# control_board_WS2812.net
KiCad netlist of a schematic drawn in EAGLE
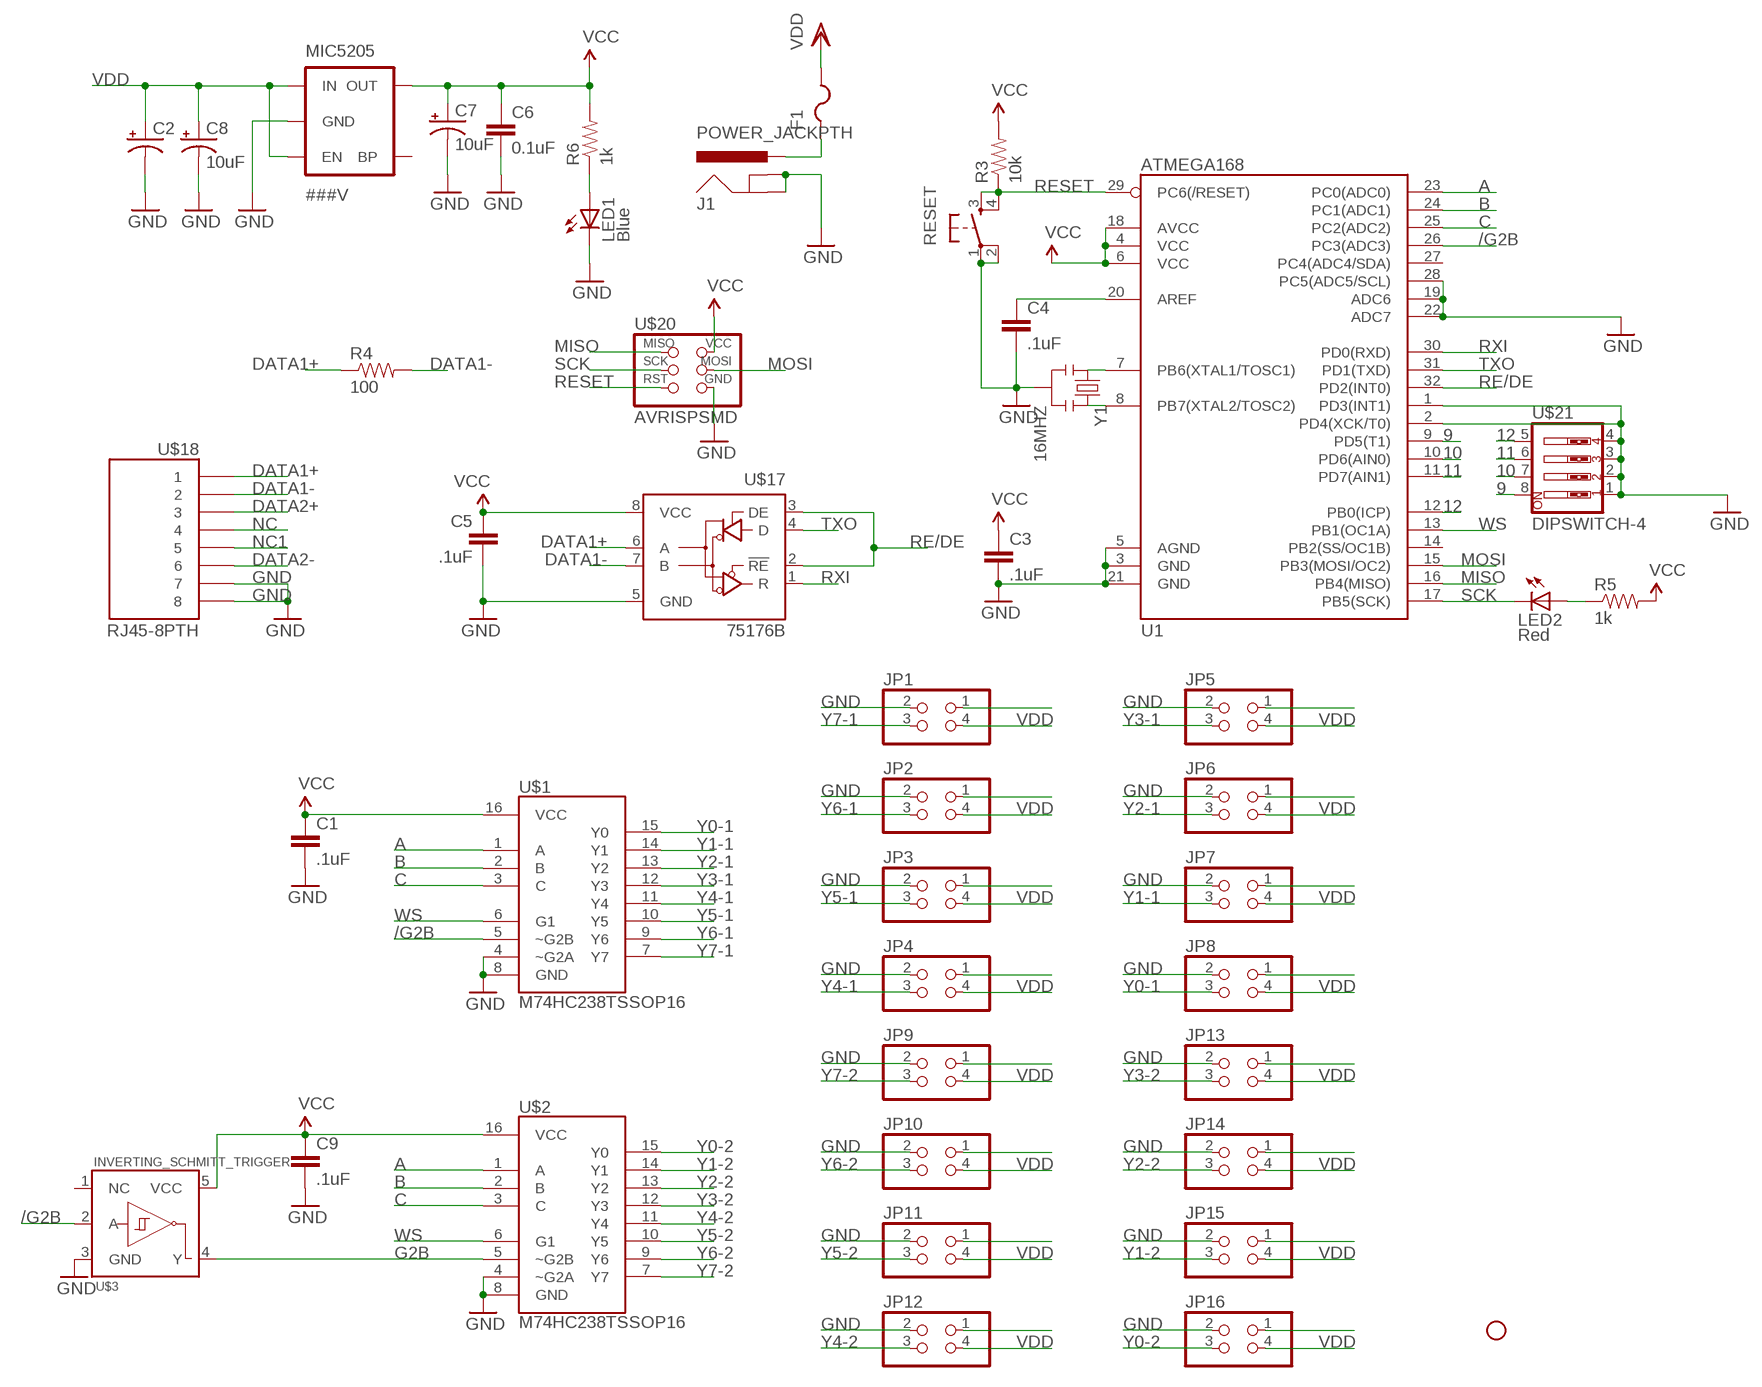
[diagram p0: schematic, sheet 1]

(export (version "E")
  (design (tool "Eeschema 10.0.6"))
  (components
    (comp (ref "C1")
      (value ".1uF")
      (footprint "eagle-import:0402-CAP")
      (libsource (lib "eagle-import") (part "CAP0402-CAP"))
    )
    (comp (ref "C2")
      (value "CAP_POLC")
      (footprint "eagle-import:PANASONIC_C")
      (libsource (lib "eagle-import") (part "CAP_POLC"))
    )
    (comp (ref "C3")
      (value ".1uF")
      (footprint "eagle-import:0402-CAP")
      (libsource (lib "eagle-import") (part "CAP0402-CAP"))
    )
    (comp (ref "C4")
      (value ".1uF")
      (footprint "eagle-import:0402-CAP")
      (libsource (lib "eagle-import") (part "CAP0402-CAP"))
    )
    (comp (ref "C5")
      (value ".1uF")
      (footprint "eagle-import:0402-CAP")
      (libsource (lib "eagle-import") (part "CAP0402-CAP"))
    )
    (comp (ref "C6")
      (value "0.1uF")
      (footprint "eagle-import:0402-CAP")
      (libsource (lib "eagle-import") (part "CAP0402-CAP"))
    )
    (comp (ref "C7")
      (value "10uF")
      (footprint "eagle-import:EIA3216")
      (libsource (lib "eagle-import") (part "CAP_POL1206"))
    )
    (comp (ref "C8")
      (value "10uF")
      (footprint "eagle-import:EIA3216")
      (libsource (lib "eagle-import") (part "CAP_POL1206"))
    )
    (comp (ref "C9")
      (value ".1uF")
      (footprint "eagle-import:0402-CAP")
      (libsource (lib "eagle-import") (part "CAP0402-CAP"))
    )
    (comp (ref "F1")
      (value "PTCFUSE-1812")
      (footprint "eagle-import:1812")
      (libsource (lib "eagle-import") (part "PTCFUSE-1812"))
    )
    (comp (ref "J1")
      (value "POWER_JACKPTH")
      (footprint "eagle-import:POWER_JACK_PTH")
      (libsource (lib "eagle-import") (part "POWER_JACKPTH"))
    )
    (comp (ref "JP1")
      (value "PINHD-2X2")
      (footprint "eagle-import:2X02")
      (libsource (lib "eagle-import") (part "PINHD-2X2"))
    )
    (comp (ref "JP2")
      (value "PINHD-2X2")
      (footprint "eagle-import:2X02")
      (libsource (lib "eagle-import") (part "PINHD-2X2"))
    )
    (comp (ref "JP3")
      (value "PINHD-2X2")
      (footprint "eagle-import:2X02")
      (libsource (lib "eagle-import") (part "PINHD-2X2"))
    )
    (comp (ref "JP4")
      (value "PINHD-2X2")
      (footprint "eagle-import:2X02")
      (libsource (lib "eagle-import") (part "PINHD-2X2"))
    )
    (comp (ref "JP5")
      (value "PINHD-2X2")
      (footprint "eagle-import:2X02")
      (libsource (lib "eagle-import") (part "PINHD-2X2"))
    )
    (comp (ref "JP6")
      (value "PINHD-2X2")
      (footprint "eagle-import:2X02")
      (libsource (lib "eagle-import") (part "PINHD-2X2"))
    )
    (comp (ref "JP7")
      (value "PINHD-2X2")
      (footprint "eagle-import:2X02")
      (libsource (lib "eagle-import") (part "PINHD-2X2"))
    )
    (comp (ref "JP8")
      (value "PINHD-2X2")
      (footprint "eagle-import:2X02")
      (libsource (lib "eagle-import") (part "PINHD-2X2"))
    )
    (comp (ref "JP9")
      (value "PINHD-2X2")
      (footprint "eagle-import:2X02")
      (libsource (lib "eagle-import") (part "PINHD-2X2"))
    )
    (comp (ref "JP10")
      (value "PINHD-2X2")
      (footprint "eagle-import:2X02")
      (libsource (lib "eagle-import") (part "PINHD-2X2"))
    )
    (comp (ref "JP11")
      (value "PINHD-2X2")
      (footprint "eagle-import:2X02")
      (libsource (lib "eagle-import") (part "PINHD-2X2"))
    )
    (comp (ref "JP12")
      (value "PINHD-2X2")
      (footprint "eagle-import:2X02")
      (libsource (lib "eagle-import") (part "PINHD-2X2"))
    )
    (comp (ref "JP13")
      (value "PINHD-2X2")
      (footprint "eagle-import:2X02")
      (libsource (lib "eagle-import") (part "PINHD-2X2"))
    )
    (comp (ref "JP14")
      (value "PINHD-2X2")
      (footprint "eagle-import:2X02")
      (libsource (lib "eagle-import") (part "PINHD-2X2"))
    )
    (comp (ref "JP15")
      (value "PINHD-2X2")
      (footprint "eagle-import:2X02")
      (libsource (lib "eagle-import") (part "PINHD-2X2"))
    )
    (comp (ref "JP16")
      (value "PINHD-2X2")
      (footprint "eagle-import:2X02")
      (libsource (lib "eagle-import") (part "PINHD-2X2"))
    )
    (comp (ref "LED1")
      (value "Blue")
      (footprint "eagle-import:LED-0603")
      (libsource (lib "eagle-import") (part "LED0603"))
    )
    (comp (ref "LED2")
      (value "Red")
      (footprint "eagle-import:LED-0603")
      (libsource (lib "eagle-import") (part "LED0603"))
    )
    (comp (ref "MIC5205")
      (value "###V")
      (footprint "eagle-import:SOT23-5")
      (libsource (lib "eagle-import") (part "V_REG_LDOSMD"))
    )
    (comp (ref "R3")
      (value "10k")
      (footprint "eagle-import:0402-RES")
      (libsource (lib "eagle-import") (part "RESISTOR0402-RES"))
    )
    (comp (ref "R4")
      (value "100")
      (footprint "eagle-import:1206")
      (libsource (lib "eagle-import") (part "SparkFun-Passives_RESISTOR1206"))
    )
    (comp (ref "R5")
      (value "1k")
      (footprint "eagle-import:C0402")
      (libsource (lib "eagle-import") (part "RESISTOR0402"))
    )
    (comp (ref "R6")
      (value "1k")
      (footprint "eagle-import:C0402")
      (libsource (lib "eagle-import") (part "RESISTOR0402"))
    )
    (comp (ref "RESET")
      (value "TAC_SWITCHSMD")
      (footprint "eagle-import:TACTILE_SWITCH_SMD")
      (libsource (lib "eagle-import") (part "TAC_SWITCHSMD"))
    )
    (comp (ref "STANDOFF1")
      (value "STAND-OFF")
      (footprint "eagle-import:STAND-OFF")
      (libsource (lib "eagle-import") (part "STAND-OFF"))
    )
    (comp (ref "U$1")
      (value "M74HC238TSSOP16")
      (footprint "eagle-import:TSSOP16")
      (libsource (lib "eagle-import") (part "M74HC238TSSOP16"))
    )
    (comp (ref "U$2")
      (value "M74HC238TSSOP16")
      (footprint "eagle-import:TSSOP16")
      (libsource (lib "eagle-import") (part "M74HC238TSSOP16"))
    )
    (comp (ref "U$3")
      (value "INVERTING_SCHMITT_TRIGGER")
      (footprint "eagle-import:TSSOP5")
      (libsource (lib "eagle-import") (part "INVERTING_SCHMITT_TRIGGER"))
    )
    (comp (ref "U$17")
      (value "75176B")
      (footprint "eagle-import:D_R-PDSO-G8")
      (libsource (lib "eagle-import") (part "75176B"))
    )
    (comp (ref "U$18")
      (value "RJ45-8PTH")
      (footprint "eagle-import:RJ45-8")
      (libsource (lib "eagle-import") (part "RJ45-8PTH"))
    )
    (comp (ref "U$20")
      (value "AVRISPSMD")
      (footprint "eagle-import:2X03SMD")
      (libsource (lib "eagle-import") (part "AVRISPSMD"))
    )
    (comp (ref "U$21")
      (value "DIPSWITCH-4")
      (footprint "eagle-import:DIPSWITCH-04")
      (libsource (lib "eagle-import") (part "DIPSWITCH-4"))
    )
    (comp (ref "U1")
      (value "ATMEGA168")
      (footprint "eagle-import:TQFP32-08")
      (libsource (lib "eagle-import") (part "ATMEGA168"))
    )
    (comp (ref "Y1")
      (value "16MHZ")
      (footprint "eagle-import:RESONATOR-SMD")
      (libsource (lib "eagle-import") (part "RESONATOR8MHZ"))
    )
  )
  (nets
    (net (code "1") (name "/9") (class "Default")
      (node (ref "U$21") (pin "8") (pinfunction "8_8") (pintype "passive"))
      (node (ref "U1") (pin "9") (pinfunction "PD5(T1)_9") (pintype "bidirectional"))
    )
    (net (code "2") (name "/10") (class "Default")
      (node (ref "U$21") (pin "7") (pinfunction "7_7") (pintype "passive"))
      (node (ref "U1") (pin "10") (pinfunction "PD6(AIN0)_10") (pintype "bidirectional"))
    )
    (net (code "3") (name "/11") (class "Default")
      (node (ref "U$21") (pin "6") (pinfunction "6_6") (pintype "passive"))
      (node (ref "U1") (pin "11") (pinfunction "PD7(AIN1)_11") (pintype "bidirectional"))
    )
    (net (code "4") (name "/12") (class "Default")
      (node (ref "U$21") (pin "5") (pinfunction "5_5") (pintype "passive"))
      (node (ref "U1") (pin "12") (pinfunction "PB0(ICP)_12") (pintype "bidirectional"))
    )
    (net (code "5") (name "/A") (class "Default")
      (node (ref "U$1") (pin "1") (pinfunction "A_1") (pintype "bidirectional"))
      (node (ref "U$2") (pin "1") (pinfunction "A_1") (pintype "bidirectional"))
      (node (ref "U1") (pin "23") (pinfunction "PC0(ADC0)_23") (pintype "bidirectional"))
    )
    (net (code "6") (name "/B") (class "Default")
      (node (ref "U$1") (pin "2") (pinfunction "B_2") (pintype "bidirectional"))
      (node (ref "U$2") (pin "2") (pinfunction "B_2") (pintype "bidirectional"))
      (node (ref "U1") (pin "24") (pinfunction "PC1(ADC1)_24") (pintype "bidirectional"))
    )
    (net (code "7") (name "/C") (class "Default")
      (node (ref "U$1") (pin "3") (pinfunction "C_3") (pintype "bidirectional"))
      (node (ref "U$2") (pin "3") (pinfunction "C_3") (pintype "bidirectional"))
      (node (ref "U1") (pin "25") (pinfunction "PC2(ADC2)_25") (pintype "bidirectional"))
    )
    (net (code "8") (name "/DATA1+") (class "Default")
      (node (ref "R4") (pin "1") (pinfunction "1_1") (pintype "passive"))
      (node (ref "U$17") (pin "6") (pinfunction "A_6") (pintype "output"))
      (node (ref "U$18") (pin "1") (pinfunction "1_1") (pintype "bidirectional"))
    )
    (net (code "9") (name "/DATA1-") (class "Default")
      (node (ref "R4") (pin "2") (pinfunction "2_2") (pintype "passive"))
      (node (ref "U$17") (pin "7") (pinfunction "B_7") (pintype "output"))
      (node (ref "U$18") (pin "2") (pinfunction "2_2") (pintype "bidirectional"))
    )
    (net (code "10") (name "/DATA2+") (class "Default")
      (node (ref "U$18") (pin "3") (pinfunction "3_3") (pintype "bidirectional"))
    )
    (net (code "11") (name "/DATA2-") (class "Default")
      (node (ref "U$18") (pin "6") (pinfunction "6_6") (pintype "bidirectional"))
    )
    (net (code "12") (name "/G2B") (class "Default")
      (node (ref "U$2") (pin "5") (pinfunction "~{G2B}_5") (pintype "bidirectional"))
      (node (ref "U$3") (pin "4") (pinfunction "Y_4") (pintype "bidirectional"))
    )
    (net (code "13") (name "/MISO") (class "Default")
      (node (ref "U$20") (pin "1") (pinfunction "MISO_1") (pintype "passive"))
      (node (ref "U1") (pin "16") (pinfunction "PB4(MISO)_16") (pintype "bidirectional"))
    )
    (net (code "14") (name "/MOSI") (class "Default")
      (node (ref "U$20") (pin "4") (pinfunction "MOSI_4") (pintype "passive"))
      (node (ref "U1") (pin "15") (pinfunction "PB3(MOSI/OC2)_15") (pintype "bidirectional"))
    )
    (net (code "15") (name "/NC") (class "Default")
      (node (ref "U$18") (pin "4") (pinfunction "4_4") (pintype "bidirectional"))
    )
    (net (code "16") (name "/NC1") (class "Default")
      (node (ref "U$18") (pin "5") (pinfunction "5_5") (pintype "bidirectional"))
    )
    (net (code "17") (name "/RESET") (class "Default")
      (node (ref "R3") (pin "1") (pinfunction "1_1") (pintype "passive"))
      (node (ref "RESET") (pin "3") (pinfunction "3_3") (pintype "passive"))
      (node (ref "RESET") (pin "4") (pinfunction "4_4") (pintype "passive"))
      (node (ref "U$20") (pin "5") (pinfunction "RST_5") (pintype "passive"))
      (node (ref "U1") (pin "29") (pinfunction "PC6(/RESET)_29") (pintype "bidirectional"))
    )
    (net (code "18") (name "/RE{slash}DE") (class "Default")
      (node (ref "U$17") (pin "2") (pinfunction "~{RE}_2") (pintype "input"))
      (node (ref "U$17") (pin "3") (pinfunction "DE_3") (pintype "input"))
      (node (ref "U1") (pin "32") (pinfunction "PD2(INT0)_32") (pintype "bidirectional"))
    )
    (net (code "19") (name "/RXI") (class "Default")
      (node (ref "U$17") (pin "1") (pinfunction "R_1") (pintype "input"))
      (node (ref "U1") (pin "30") (pinfunction "PD0(RXD)_30") (pintype "bidirectional"))
    )
    (net (code "20") (name "/SCK") (class "Default")
      (node (ref "LED2") (pin "C") (pinfunction "C_C") (pintype "passive"))
      (node (ref "U$20") (pin "3") (pinfunction "SCK_3") (pintype "passive"))
      (node (ref "U1") (pin "17") (pinfunction "PB5(SCK)_17") (pintype "bidirectional"))
    )
    (net (code "21") (name "/TXO") (class "Default")
      (node (ref "U$17") (pin "4") (pinfunction "D_4") (pintype "input"))
      (node (ref "U1") (pin "31") (pinfunction "PD1(TXD)_31") (pintype "bidirectional"))
    )
    (net (code "22") (name "/WS") (class "Default")
      (node (ref "U$1") (pin "6") (pinfunction "G1_6") (pintype "bidirectional"))
      (node (ref "U$2") (pin "6") (pinfunction "G1_6") (pintype "bidirectional"))
      (node (ref "U1") (pin "13") (pinfunction "PB1(OC1A)_13") (pintype "bidirectional"))
    )
    (net (code "23") (name "/Y0-1") (class "Default")
      (node (ref "JP8") (pin "3") (pinfunction "3_3") (pintype "passive"))
      (node (ref "U$1") (pin "15") (pinfunction "Y0_15") (pintype "bidirectional"))
    )
    (net (code "24") (name "/Y0-2") (class "Default")
      (node (ref "JP16") (pin "3") (pinfunction "3_3") (pintype "passive"))
      (node (ref "U$2") (pin "15") (pinfunction "Y0_15") (pintype "bidirectional"))
    )
    (net (code "25") (name "/Y1-1") (class "Default")
      (node (ref "JP7") (pin "3") (pinfunction "3_3") (pintype "passive"))
      (node (ref "U$1") (pin "14") (pinfunction "Y1_14") (pintype "bidirectional"))
    )
    (net (code "26") (name "/Y1-2") (class "Default")
      (node (ref "JP15") (pin "3") (pinfunction "3_3") (pintype "passive"))
      (node (ref "U$2") (pin "14") (pinfunction "Y1_14") (pintype "bidirectional"))
    )
    (net (code "27") (name "/Y2-1") (class "Default")
      (node (ref "JP6") (pin "3") (pinfunction "3_3") (pintype "passive"))
      (node (ref "U$1") (pin "13") (pinfunction "Y2_13") (pintype "bidirectional"))
    )
    (net (code "28") (name "/Y2-2") (class "Default")
      (node (ref "JP14") (pin "3") (pinfunction "3_3") (pintype "passive"))
      (node (ref "U$2") (pin "13") (pinfunction "Y2_13") (pintype "bidirectional"))
    )
    (net (code "29") (name "/Y3-1") (class "Default")
      (node (ref "JP5") (pin "3") (pinfunction "3_3") (pintype "passive"))
      (node (ref "U$1") (pin "12") (pinfunction "Y3_12") (pintype "bidirectional"))
    )
    (net (code "30") (name "/Y3-2") (class "Default")
      (node (ref "JP13") (pin "3") (pinfunction "3_3") (pintype "passive"))
      (node (ref "U$2") (pin "12") (pinfunction "Y3_12") (pintype "bidirectional"))
    )
    (net (code "31") (name "/Y4-1") (class "Default")
      (node (ref "JP4") (pin "3") (pinfunction "3_3") (pintype "passive"))
      (node (ref "U$1") (pin "11") (pinfunction "Y4_11") (pintype "bidirectional"))
    )
    (net (code "32") (name "/Y4-2") (class "Default")
      (node (ref "JP12") (pin "3") (pinfunction "3_3") (pintype "passive"))
      (node (ref "U$2") (pin "11") (pinfunction "Y4_11") (pintype "bidirectional"))
    )
    (net (code "33") (name "/Y5-1") (class "Default")
      (node (ref "JP3") (pin "3") (pinfunction "3_3") (pintype "passive"))
      (node (ref "U$1") (pin "10") (pinfunction "Y5_10") (pintype "bidirectional"))
    )
    (net (code "34") (name "/Y5-2") (class "Default")
      (node (ref "JP11") (pin "3") (pinfunction "3_3") (pintype "passive"))
      (node (ref "U$2") (pin "10") (pinfunction "Y5_10") (pintype "bidirectional"))
    )
    (net (code "35") (name "/Y6-1") (class "Default")
      (node (ref "JP2") (pin "3") (pinfunction "3_3") (pintype "passive"))
      (node (ref "U$1") (pin "9") (pinfunction "Y6_9") (pintype "bidirectional"))
    )
    (net (code "36") (name "/Y6-2") (class "Default")
      (node (ref "JP10") (pin "3") (pinfunction "3_3") (pintype "passive"))
      (node (ref "U$2") (pin "9") (pinfunction "Y6_9") (pintype "bidirectional"))
    )
    (net (code "37") (name "/Y7-1") (class "Default")
      (node (ref "JP1") (pin "3") (pinfunction "3_3") (pintype "passive"))
      (node (ref "U$1") (pin "7") (pinfunction "Y7_7") (pintype "bidirectional"))
    )
    (net (code "38") (name "/Y7-2") (class "Default")
      (node (ref "JP9") (pin "3") (pinfunction "3_3") (pintype "passive"))
      (node (ref "U$2") (pin "7") (pinfunction "Y7_7") (pintype "bidirectional"))
    )
    (net (code "39") (name "/{slash}G2B") (class "Default")
      (node (ref "U$1") (pin "5") (pinfunction "~{G2B}_5") (pintype "bidirectional"))
      (node (ref "U$3") (pin "2") (pinfunction "A_2") (pintype "bidirectional"))
      (node (ref "U1") (pin "26") (pinfunction "PC3(ADC3)_26") (pintype "bidirectional"))
    )
    (net (code "40") (name "GND") (class "Default")
      (node (ref "C1") (pin "2") (pinfunction "2_2") (pintype "passive"))
      (node (ref "C2") (pin "-") (pinfunction "-_-") (pintype "passive"))
      (node (ref "C3") (pin "2") (pinfunction "2_2") (pintype "passive"))
      (node (ref "C4") (pin "2") (pinfunction "2_2") (pintype "passive"))
      (node (ref "C5") (pin "2") (pinfunction "2_2") (pintype "passive"))
      (node (ref "C6") (pin "2") (pinfunction "2_2") (pintype "passive"))
      (node (ref "C7") (pin "C") (pinfunction "-_C") (pintype "passive"))
      (node (ref "C8") (pin "C") (pinfunction "-_C") (pintype "passive"))
      (node (ref "C9") (pin "2") (pinfunction "2_2") (pintype "passive"))
      (node (ref "J1") (pin "GND") (pinfunction "GND_GND") (pintype "bidirectional"))
      (node (ref "J1") (pin "GNDBREAK") (pinfunction "GNDBREAK_GNDBREAK") (pintype "bidirectional"))
      (node (ref "JP1") (pin "2") (pinfunction "2_2") (pintype "passive"))
      (node (ref "JP10") (pin "2") (pinfunction "2_2") (pintype "passive"))
      (node (ref "JP11") (pin "2") (pinfunction "2_2") (pintype "passive"))
      (node (ref "JP12") (pin "2") (pinfunction "2_2") (pintype "passive"))
      (node (ref "JP13") (pin "2") (pinfunction "2_2") (pintype "passive"))
      (node (ref "JP14") (pin "2") (pinfunction "2_2") (pintype "passive"))
      (node (ref "JP15") (pin "2") (pinfunction "2_2") (pintype "passive"))
      (node (ref "JP16") (pin "2") (pinfunction "2_2") (pintype "passive"))
      (node (ref "JP2") (pin "2") (pinfunction "2_2") (pintype "passive"))
      (node (ref "JP3") (pin "2") (pinfunction "2_2") (pintype "passive"))
      (node (ref "JP4") (pin "2") (pinfunction "2_2") (pintype "passive"))
      (node (ref "JP5") (pin "2") (pinfunction "2_2") (pintype "passive"))
      (node (ref "JP6") (pin "2") (pinfunction "2_2") (pintype "passive"))
      (node (ref "JP7") (pin "2") (pinfunction "2_2") (pintype "passive"))
      (node (ref "JP8") (pin "2") (pinfunction "2_2") (pintype "passive"))
      (node (ref "JP9") (pin "2") (pinfunction "2_2") (pintype "passive"))
      (node (ref "LED1") (pin "C") (pinfunction "C_C") (pintype "passive"))
      (node (ref "MIC5205") (pin "2") (pinfunction "GND_2") (pintype "input"))
      (node (ref "RESET") (pin "1") (pinfunction "1_1") (pintype "passive"))
      (node (ref "RESET") (pin "2") (pinfunction "2_2") (pintype "passive"))
      (node (ref "U$1") (pin "4") (pinfunction "~{G2A}_4") (pintype "bidirectional"))
      (node (ref "U$1") (pin "8") (pinfunction "GND_8") (pintype "bidirectional"))
      (node (ref "U$17") (pin "5") (pinfunction "GND_5") (pintype "power_in"))
      (node (ref "U$18") (pin "7") (pinfunction "7_7") (pintype "bidirectional"))
      (node (ref "U$18") (pin "8") (pinfunction "8_8") (pintype "bidirectional"))
      (node (ref "U$2") (pin "4") (pinfunction "~{G2A}_4") (pintype "bidirectional"))
      (node (ref "U$2") (pin "8") (pinfunction "GND_8") (pintype "bidirectional"))
      (node (ref "U$20") (pin "6") (pinfunction "GND_6") (pintype "passive"))
      (node (ref "U$21") (pin "1") (pinfunction "1_1") (pintype "passive"))
      (node (ref "U$21") (pin "2") (pinfunction "2_2") (pintype "passive"))
      (node (ref "U$21") (pin "3") (pinfunction "3_3") (pintype "passive"))
      (node (ref "U$21") (pin "4") (pinfunction "4_4") (pintype "passive"))
      (node (ref "U$3") (pin "3") (pinfunction "GND_3") (pintype "bidirectional"))
      (node (ref "U1") (pin "1") (pinfunction "PD3(INT1)_1") (pintype "bidirectional"))
      (node (ref "U1") (pin "19") (pinfunction "ADC6_19") (pintype "bidirectional"))
      (node (ref "U1") (pin "2") (pinfunction "PD4(XCK/T0)_2") (pintype "bidirectional"))
      (node (ref "U1") (pin "21") (pinfunction "GND_21") (pintype "bidirectional"))
      (node (ref "U1") (pin "22") (pinfunction "ADC7_22") (pintype "bidirectional"))
      (node (ref "U1") (pin "28") (pinfunction "PC5(ADC5/SCL)_28") (pintype "bidirectional"))
      (node (ref "U1") (pin "3") (pinfunction "GND_3") (pintype "bidirectional"))
      (node (ref "U1") (pin "5") (pinfunction "AGND_5") (pintype "bidirectional"))
      (node (ref "Y1") (pin "2") (pinfunction "2_2") (pintype "passive"))
    )
    (net (code "41") (name "Net-(F1-Pad1)") (class "Default")
      (node (ref "F1") (pin "1") (pinfunction "1_1") (pintype "passive"))
      (node (ref "J1") (pin "PWR") (pinfunction "PWR_PWR") (pintype "bidirectional"))
    )
    (net (code "42") (name "Net-(LED1-PadA)") (class "Default")
      (node (ref "LED1") (pin "A") (pinfunction "A_A") (pintype "passive"))
      (node (ref "R6") (pin "1") (pinfunction "1_1") (pintype "passive"))
    )
    (net (code "43") (name "Net-(LED2-PadA)") (class "Default")
      (node (ref "LED2") (pin "A") (pinfunction "A_A") (pintype "passive"))
      (node (ref "R5") (pin "1") (pinfunction "1_1") (pintype "passive"))
    )
    (net (code "44") (name "Net-(U1-AREF)") (class "Default")
      (node (ref "C4") (pin "1") (pinfunction "1_1") (pintype "passive"))
      (node (ref "U1") (pin "20") (pinfunction "AREF_20") (pintype "bidirectional"))
    )
    (net (code "45") (name "Net-(U1-PB6(XTAL1{slash}TOSC1))") (class "Default")
      (node (ref "U1") (pin "7") (pinfunction "PB6(XTAL1/TOSC1)_7") (pintype "bidirectional"))
      (node (ref "Y1") (pin "1") (pinfunction "1_1") (pintype "passive"))
    )
    (net (code "46") (name "Net-(U1-PB7(XTAL2{slash}TOSC2))") (class "Default")
      (node (ref "U1") (pin "8") (pinfunction "PB7(XTAL2/TOSC2)_8") (pintype "bidirectional"))
      (node (ref "Y1") (pin "3") (pinfunction "3_3") (pintype "passive"))
    )
    (net (code "47") (name "VCC") (class "Default")
      (node (ref "C1") (pin "1") (pinfunction "1_1") (pintype "passive"))
      (node (ref "C3") (pin "1") (pinfunction "1_1") (pintype "passive"))
      (node (ref "C5") (pin "1") (pinfunction "1_1") (pintype "passive"))
      (node (ref "C6") (pin "1") (pinfunction "1_1") (pintype "passive"))
      (node (ref "C7") (pin "A") (pinfunction "+_A") (pintype "passive"))
      (node (ref "C9") (pin "1") (pinfunction "1_1") (pintype "passive"))
      (node (ref "MIC5205") (pin "5") (pinfunction "OUT_5") (pintype "passive"))
      (node (ref "R3") (pin "2") (pinfunction "2_2") (pintype "passive"))
      (node (ref "R5") (pin "2") (pinfunction "2_2") (pintype "passive"))
      (node (ref "R6") (pin "2") (pinfunction "2_2") (pintype "passive"))
      (node (ref "U$1") (pin "16") (pinfunction "VCC_16") (pintype "bidirectional"))
      (node (ref "U$17") (pin "8") (pinfunction "VCC_8") (pintype "power_in"))
      (node (ref "U$2") (pin "16") (pinfunction "VCC_16") (pintype "bidirectional"))
      (node (ref "U$20") (pin "2") (pinfunction "VCC_2") (pintype "passive"))
      (node (ref "U$3") (pin "5") (pinfunction "VCC_5") (pintype "bidirectional"))
      (node (ref "U1") (pin "18") (pinfunction "AVCC_18") (pintype "bidirectional"))
      (node (ref "U1") (pin "4") (pinfunction "VCC_4") (pintype "bidirectional"))
      (node (ref "U1") (pin "6") (pinfunction "VCC_6") (pintype "bidirectional"))
    )
    (net (code "48") (name "VDD") (class "Default")
      (node (ref "C2") (pin "+") (pinfunction "+_+") (pintype "passive"))
      (node (ref "C8") (pin "A") (pinfunction "+_A") (pintype "passive"))
      (node (ref "F1") (pin "2") (pinfunction "2_2") (pintype "passive"))
      (node (ref "JP1") (pin "4") (pinfunction "4_4") (pintype "passive"))
      (node (ref "JP10") (pin "4") (pinfunction "4_4") (pintype "passive"))
      (node (ref "JP11") (pin "4") (pinfunction "4_4") (pintype "passive"))
      (node (ref "JP12") (pin "4") (pinfunction "4_4") (pintype "passive"))
      (node (ref "JP13") (pin "4") (pinfunction "4_4") (pintype "passive"))
      (node (ref "JP14") (pin "4") (pinfunction "4_4") (pintype "passive"))
      (node (ref "JP15") (pin "4") (pinfunction "4_4") (pintype "passive"))
      (node (ref "JP16") (pin "4") (pinfunction "4_4") (pintype "passive"))
      (node (ref "JP2") (pin "4") (pinfunction "4_4") (pintype "passive"))
      (node (ref "JP3") (pin "4") (pinfunction "4_4") (pintype "passive"))
      (node (ref "JP4") (pin "4") (pinfunction "4_4") (pintype "passive"))
      (node (ref "JP5") (pin "4") (pinfunction "4_4") (pintype "passive"))
      (node (ref "JP6") (pin "4") (pinfunction "4_4") (pintype "passive"))
      (node (ref "JP7") (pin "4") (pinfunction "4_4") (pintype "passive"))
      (node (ref "JP8") (pin "4") (pinfunction "4_4") (pintype "passive"))
      (node (ref "JP9") (pin "4") (pinfunction "4_4") (pintype "passive"))
      (node (ref "MIC5205") (pin "1") (pinfunction "IN_1") (pintype "input"))
      (node (ref "MIC5205") (pin "3") (pinfunction "EN_3") (pintype "input"))
    )
    (net (code "49") (name "unconnected-(JP1-Pad1)") (class "Default")
      (node (ref "JP1") (pin "1") (pinfunction "1_1") (pintype "passive"))
    )
    (net (code "50") (name "unconnected-(JP2-Pad1)") (class "Default")
      (node (ref "JP2") (pin "1") (pinfunction "1_1") (pintype "passive"))
    )
    (net (code "51") (name "unconnected-(JP3-Pad1)") (class "Default")
      (node (ref "JP3") (pin "1") (pinfunction "1_1") (pintype "passive"))
    )
    (net (code "52") (name "unconnected-(JP4-Pad1)") (class "Default")
      (node (ref "JP4") (pin "1") (pinfunction "1_1") (pintype "passive"))
    )
    (net (code "53") (name "unconnected-(JP5-Pad1)") (class "Default")
      (node (ref "JP5") (pin "1") (pinfunction "1_1") (pintype "passive"))
    )
    (net (code "54") (name "unconnected-(JP6-Pad1)") (class "Default")
      (node (ref "JP6") (pin "1") (pinfunction "1_1") (pintype "passive"))
    )
    (net (code "55") (name "unconnected-(JP7-Pad1)") (class "Default")
      (node (ref "JP7") (pin "1") (pinfunction "1_1") (pintype "passive"))
    )
    (net (code "56") (name "unconnected-(JP8-Pad1)") (class "Default")
      (node (ref "JP8") (pin "1") (pinfunction "1_1") (pintype "passive"))
    )
    (net (code "57") (name "unconnected-(JP9-Pad1)") (class "Default")
      (node (ref "JP9") (pin "1") (pinfunction "1_1") (pintype "passive"))
    )
    (net (code "58") (name "unconnected-(JP10-Pad1)") (class "Default")
      (node (ref "JP10") (pin "1") (pinfunction "1_1") (pintype "passive"))
    )
    (net (code "59") (name "unconnected-(JP11-Pad1)") (class "Default")
      (node (ref "JP11") (pin "1") (pinfunction "1_1") (pintype "passive"))
    )
    (net (code "60") (name "unconnected-(JP12-Pad1)") (class "Default")
      (node (ref "JP12") (pin "1") (pinfunction "1_1") (pintype "passive"))
    )
    (net (code "61") (name "unconnected-(JP13-Pad1)") (class "Default")
      (node (ref "JP13") (pin "1") (pinfunction "1_1") (pintype "passive"))
    )
    (net (code "62") (name "unconnected-(JP14-Pad1)") (class "Default")
      (node (ref "JP14") (pin "1") (pinfunction "1_1") (pintype "passive"))
    )
    (net (code "63") (name "unconnected-(JP15-Pad1)") (class "Default")
      (node (ref "JP15") (pin "1") (pinfunction "1_1") (pintype "passive"))
    )
    (net (code "64") (name "unconnected-(JP16-Pad1)") (class "Default")
      (node (ref "JP16") (pin "1") (pinfunction "1_1") (pintype "passive"))
    )
    (net (code "65") (name "unconnected-(MIC5205-BP-Pad4)") (class "Default")
      (node (ref "MIC5205") (pin "4") (pinfunction "BP_4") (pintype "input"))
    )
    (net (code "66") (name "unconnected-(U$3-NC-Pad1)") (class "Default")
      (node (ref "U$3") (pin "1") (pinfunction "NC_1") (pintype "bidirectional"))
    )
    (net (code "67") (name "unconnected-(U1-PB2(SS{slash}OC1B)-Pad14)") (class "Default")
      (node (ref "U1") (pin "14") (pinfunction "PB2(SS/OC1B)_14") (pintype "bidirectional"))
    )
    (net (code "68") (name "unconnected-(U1-PC4(ADC4{slash}SDA)-Pad27)") (class "Default")
      (node (ref "U1") (pin "27") (pinfunction "PC4(ADC4/SDA)_27") (pintype "bidirectional"))
    )
  )
)
